# SpiderBackV1.net
KiCad netlist of a schematic drawn in EAGLE
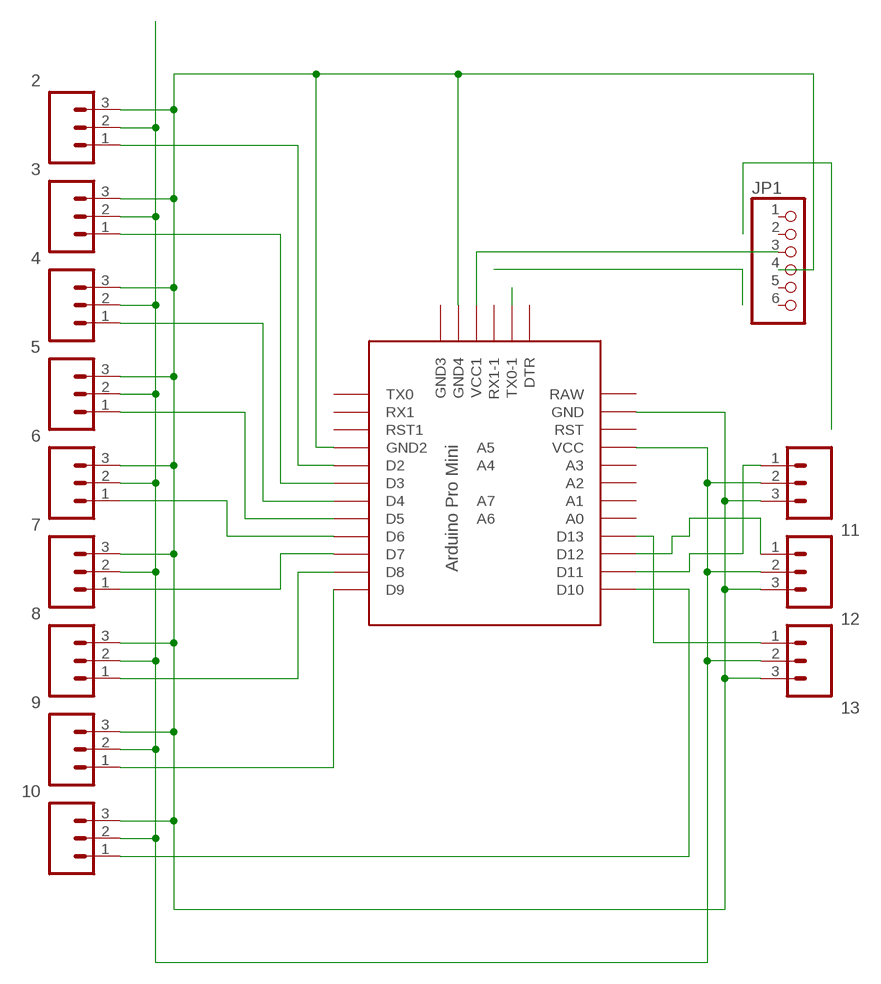
[diagram p0: schematic, sheet 1]

(export (version "E")
  (design (tool "Eeschema 10.0.6"))
  (components
    (comp (ref "2")
      (value "M03PTH")
      (footprint "eagle-import:1X03")
      (libsource (lib "eagle-import") (part "M03PTH"))
    )
    (comp (ref "3")
      (value "M03PTH")
      (footprint "eagle-import:1X03")
      (libsource (lib "eagle-import") (part "M03PTH"))
    )
    (comp (ref "4")
      (value "M03PTH")
      (footprint "eagle-import:1X03")
      (libsource (lib "eagle-import") (part "M03PTH"))
    )
    (comp (ref "5")
      (value "M03PTH")
      (footprint "eagle-import:1X03")
      (libsource (lib "eagle-import") (part "M03PTH"))
    )
    (comp (ref "6")
      (value "M03PTH")
      (footprint "eagle-import:1X03")
      (libsource (lib "eagle-import") (part "M03PTH"))
    )
    (comp (ref "7")
      (value "M03PTH")
      (footprint "eagle-import:1X03")
      (libsource (lib "eagle-import") (part "M03PTH"))
    )
    (comp (ref "8")
      (value "M03PTH")
      (footprint "eagle-import:1X03")
      (libsource (lib "eagle-import") (part "M03PTH"))
    )
    (comp (ref "9")
      (value "M03PTH")
      (footprint "eagle-import:1X03")
      (libsource (lib "eagle-import") (part "M03PTH"))
    )
    (comp (ref "10")
      (value "M03PTH")
      (footprint "eagle-import:1X03")
      (libsource (lib "eagle-import") (part "M03PTH"))
    )
    (comp (ref "11")
      (value "M03PTH")
      (footprint "eagle-import:1X03")
      (libsource (lib "eagle-import") (part "M03PTH"))
    )
    (comp (ref "12")
      (value "M03PTH")
      (footprint "eagle-import:1X03")
      (libsource (lib "eagle-import") (part "M03PTH"))
    )
    (comp (ref "13")
      (value "M03PTH")
      (footprint "eagle-import:1X03")
      (libsource (lib "eagle-import") (part "M03PTH"))
    )
    (comp (ref "JP1")
      (value "PINHD-1X6CB")
      (footprint "eagle-import:1X06-CLEANBIG")
      (libsource (lib "eagle-import") (part "PINHD-1X6CB"))
    )
    (comp (ref "U$1")
      (value "PRO-MINI-2")
      (footprint "eagle-import:PRO-MINI-2")
      (libsource (lib "eagle-import") (part "PRO-MINI-2"))
    )
  )
  (nets
    (net (code "1") (name "Net-(2-Pad1)") (class "Default")
      (node (ref "2") (pin "1") (pinfunction "1_1") (pintype "passive"))
      (node (ref "U$1") (pin "D2") (pinfunction "D2_D2") (pintype "bidirectional"))
    )
    (net (code "2") (name "Net-(3-Pad1)") (class "Default")
      (node (ref "3") (pin "1") (pinfunction "1_1") (pintype "passive"))
      (node (ref "U$1") (pin "D3") (pinfunction "D3_D3") (pintype "bidirectional"))
    )
    (net (code "3") (name "Net-(4-Pad1)") (class "Default")
      (node (ref "4") (pin "1") (pinfunction "1_1") (pintype "passive"))
      (node (ref "U$1") (pin "D4") (pinfunction "D4_D4") (pintype "bidirectional"))
    )
    (net (code "4") (name "Net-(5-Pad1)") (class "Default")
      (node (ref "5") (pin "1") (pinfunction "1_1") (pintype "passive"))
      (node (ref "U$1") (pin "D5") (pinfunction "D5_D5") (pintype "bidirectional"))
    )
    (net (code "5") (name "Net-(6-Pad1)") (class "Default")
      (node (ref "6") (pin "1") (pinfunction "1_1") (pintype "passive"))
      (node (ref "U$1") (pin "D6") (pinfunction "D6_D6") (pintype "bidirectional"))
    )
    (net (code "6") (name "Net-(7-Pad1)") (class "Default")
      (node (ref "7") (pin "1") (pinfunction "1_1") (pintype "passive"))
      (node (ref "U$1") (pin "D7") (pinfunction "D7_D7") (pintype "bidirectional"))
    )
    (net (code "7") (name "Net-(8-Pad1)") (class "Default")
      (node (ref "8") (pin "1") (pinfunction "1_1") (pintype "passive"))
      (node (ref "U$1") (pin "D8") (pinfunction "D8_D8") (pintype "bidirectional"))
    )
    (net (code "8") (name "Net-(9-Pad1)") (class "Default")
      (node (ref "9") (pin "1") (pinfunction "1_1") (pintype "passive"))
      (node (ref "U$1") (pin "D9") (pinfunction "D9_D9") (pintype "bidirectional"))
    )
    (net (code "9") (name "Net-(10-Pad1)") (class "Default")
      (node (ref "10") (pin "1") (pinfunction "1_1") (pintype "passive"))
      (node (ref "U$1") (pin "D10") (pinfunction "D10_D10") (pintype "bidirectional"))
    )
    (net (code "10") (name "Net-(10-Pad2)") (class "Default")
      (node (ref "10") (pin "2") (pinfunction "2_2") (pintype "passive"))
      (node (ref "11") (pin "2") (pinfunction "2_2") (pintype "passive"))
      (node (ref "12") (pin "2") (pinfunction "2_2") (pintype "passive"))
      (node (ref "13") (pin "2") (pinfunction "2_2") (pintype "passive"))
      (node (ref "2") (pin "2") (pinfunction "2_2") (pintype "passive"))
      (node (ref "3") (pin "2") (pinfunction "2_2") (pintype "passive"))
      (node (ref "4") (pin "2") (pinfunction "2_2") (pintype "passive"))
      (node (ref "5") (pin "2") (pinfunction "2_2") (pintype "passive"))
      (node (ref "6") (pin "2") (pinfunction "2_2") (pintype "passive"))
      (node (ref "7") (pin "2") (pinfunction "2_2") (pintype "passive"))
      (node (ref "8") (pin "2") (pinfunction "2_2") (pintype "passive"))
      (node (ref "9") (pin "2") (pinfunction "2_2") (pintype "passive"))
      (node (ref "U$1") (pin "VCC") (pinfunction "VCC_VCC") (pintype "bidirectional"))
    )
    (net (code "11") (name "Net-(11-Pad1)") (class "Default")
      (node (ref "11") (pin "1") (pinfunction "1_1") (pintype "passive"))
      (node (ref "U$1") (pin "D11") (pinfunction "D11_D11") (pintype "bidirectional"))
    )
    (net (code "12") (name "Net-(12-Pad1)") (class "Default")
      (node (ref "12") (pin "1") (pinfunction "1_1") (pintype "passive"))
      (node (ref "U$1") (pin "D12") (pinfunction "D12_D12") (pintype "bidirectional"))
    )
    (net (code "13") (name "Net-(13-Pad1)") (class "Default")
      (node (ref "13") (pin "1") (pinfunction "1_1") (pintype "passive"))
      (node (ref "U$1") (pin "D13") (pinfunction "D13_D13") (pintype "bidirectional"))
    )
    (net (code "14") (name "Net-(JP1-Pad3)") (class "Default")
      (node (ref "JP1") (pin "3") (pinfunction "3_3") (pintype "passive"))
      (node (ref "U$1") (pin "VCC1") (pinfunction "VCC1_VCC1") (pintype "bidirectional"))
    )
    (net (code "15") (name "Net-(U$1-GND2)") (class "Default")
      (node (ref "10") (pin "3") (pinfunction "3_3") (pintype "passive"))
      (node (ref "11") (pin "3") (pinfunction "3_3") (pintype "passive"))
      (node (ref "12") (pin "3") (pinfunction "3_3") (pintype "passive"))
      (node (ref "13") (pin "3") (pinfunction "3_3") (pintype "passive"))
      (node (ref "2") (pin "3") (pinfunction "3_3") (pintype "passive"))
      (node (ref "3") (pin "3") (pinfunction "3_3") (pintype "passive"))
      (node (ref "4") (pin "3") (pinfunction "3_3") (pintype "passive"))
      (node (ref "5") (pin "3") (pinfunction "3_3") (pintype "passive"))
      (node (ref "6") (pin "3") (pinfunction "3_3") (pintype "passive"))
      (node (ref "7") (pin "3") (pinfunction "3_3") (pintype "passive"))
      (node (ref "8") (pin "3") (pinfunction "3_3") (pintype "passive"))
      (node (ref "9") (pin "3") (pinfunction "3_3") (pintype "passive"))
      (node (ref "JP1") (pin "4") (pinfunction "4_4") (pintype "passive"))
      (node (ref "U$1") (pin "GND") (pinfunction "GND_GND") (pintype "bidirectional"))
      (node (ref "U$1") (pin "GND1") (pinfunction "GND2_GND1") (pintype "bidirectional"))
      (node (ref "U$1") (pin "GND3") (pinfunction "GND4_GND3") (pintype "bidirectional"))
    )
    (net (code "16") (name "unconnected-(JP1-Pad1)") (class "Default")
      (node (ref "JP1") (pin "1") (pinfunction "1_1") (pintype "passive"))
    )
    (net (code "17") (name "unconnected-(JP1-Pad2)") (class "Default")
      (node (ref "JP1") (pin "2") (pinfunction "2_2") (pintype "passive"))
    )
    (net (code "18") (name "unconnected-(JP1-Pad5)") (class "Default")
      (node (ref "JP1") (pin "5") (pinfunction "5_5") (pintype "passive"))
    )
    (net (code "19") (name "unconnected-(JP1-Pad6)") (class "Default")
      (node (ref "JP1") (pin "6") (pinfunction "6_6") (pintype "passive"))
    )
    (net (code "20") (name "unconnected-(U$1-GND3-PadGND2)") (class "Default")
      (node (ref "U$1") (pin "GND2") (pinfunction "GND3_GND2") (pintype "bidirectional"))
    )
    (net (code "21") (name "unconnected-(U$1-PadA0)") (class "Default")
      (node (ref "U$1") (pin "A0") (pinfunction "A0_A0") (pintype "bidirectional"))
    )
    (net (code "22") (name "unconnected-(U$1-PadA1)") (class "Default")
      (node (ref "U$1") (pin "A1") (pinfunction "A1_A1") (pintype "bidirectional"))
    )
    (net (code "23") (name "unconnected-(U$1-PadA2)") (class "Default")
      (node (ref "U$1") (pin "A2") (pinfunction "A2_A2") (pintype "bidirectional"))
    )
    (net (code "24") (name "unconnected-(U$1-PadA3)") (class "Default")
      (node (ref "U$1") (pin "A3") (pinfunction "A3_A3") (pintype "bidirectional"))
    )
    (net (code "25") (name "unconnected-(U$1-PadA4)") (class "Default")
      (node (ref "U$1") (pin "A4") (pinfunction "A4_A4") (pintype "bidirectional"))
    )
    (net (code "26") (name "unconnected-(U$1-PadA5)") (class "Default")
      (node (ref "U$1") (pin "A5") (pinfunction "A5_A5") (pintype "bidirectional"))
    )
    (net (code "27") (name "unconnected-(U$1-PadA6)") (class "Default")
      (node (ref "U$1") (pin "A6") (pinfunction "A6_A6") (pintype "bidirectional"))
    )
    (net (code "28") (name "unconnected-(U$1-PadA7)") (class "Default")
      (node (ref "U$1") (pin "A7") (pinfunction "A7_A7") (pintype "bidirectional"))
    )
    (net (code "29") (name "unconnected-(U$1-PadDTR)") (class "Default")
      (node (ref "U$1") (pin "DTR") (pinfunction "DTR_DTR") (pintype "bidirectional"))
    )
    (net (code "30") (name "unconnected-(U$1-PadRAW)") (class "Default")
      (node (ref "U$1") (pin "RAW") (pinfunction "RAW_RAW") (pintype "bidirectional"))
    )
    (net (code "31") (name "unconnected-(U$1-PadRST)") (class "Default")
      (node (ref "U$1") (pin "RST") (pinfunction "RST_RST") (pintype "bidirectional"))
    )
    (net (code "32") (name "unconnected-(U$1-PadRST1)") (class "Default")
      (node (ref "U$1") (pin "RST1") (pinfunction "RST1_RST1") (pintype "bidirectional"))
    )
    (net (code "33") (name "unconnected-(U$1-PadRX1)") (class "Default")
      (node (ref "U$1") (pin "RX1") (pinfunction "RX1_RX1") (pintype "bidirectional"))
    )
    (net (code "34") (name "unconnected-(U$1-PadRX1-1)") (class "Default")
      (node (ref "U$1") (pin "RX1-1") (pinfunction "RX1-1_RX1-1") (pintype "bidirectional"))
    )
    (net (code "35") (name "unconnected-(U$1-PadTX0)") (class "Default")
      (node (ref "U$1") (pin "TX0") (pinfunction "TX0_TX0") (pintype "bidirectional"))
    )
    (net (code "36") (name "unconnected-(U$1-PadTX0-1)") (class "Default")
      (node (ref "U$1") (pin "TX0-1") (pinfunction "TX0-1_TX0-1") (pintype "bidirectional"))
    )
  )
)
